# SCH_Hub-USB-Adrian_2025-03-06.net
KiCad netlist of a schematic drawn in EasyEDA
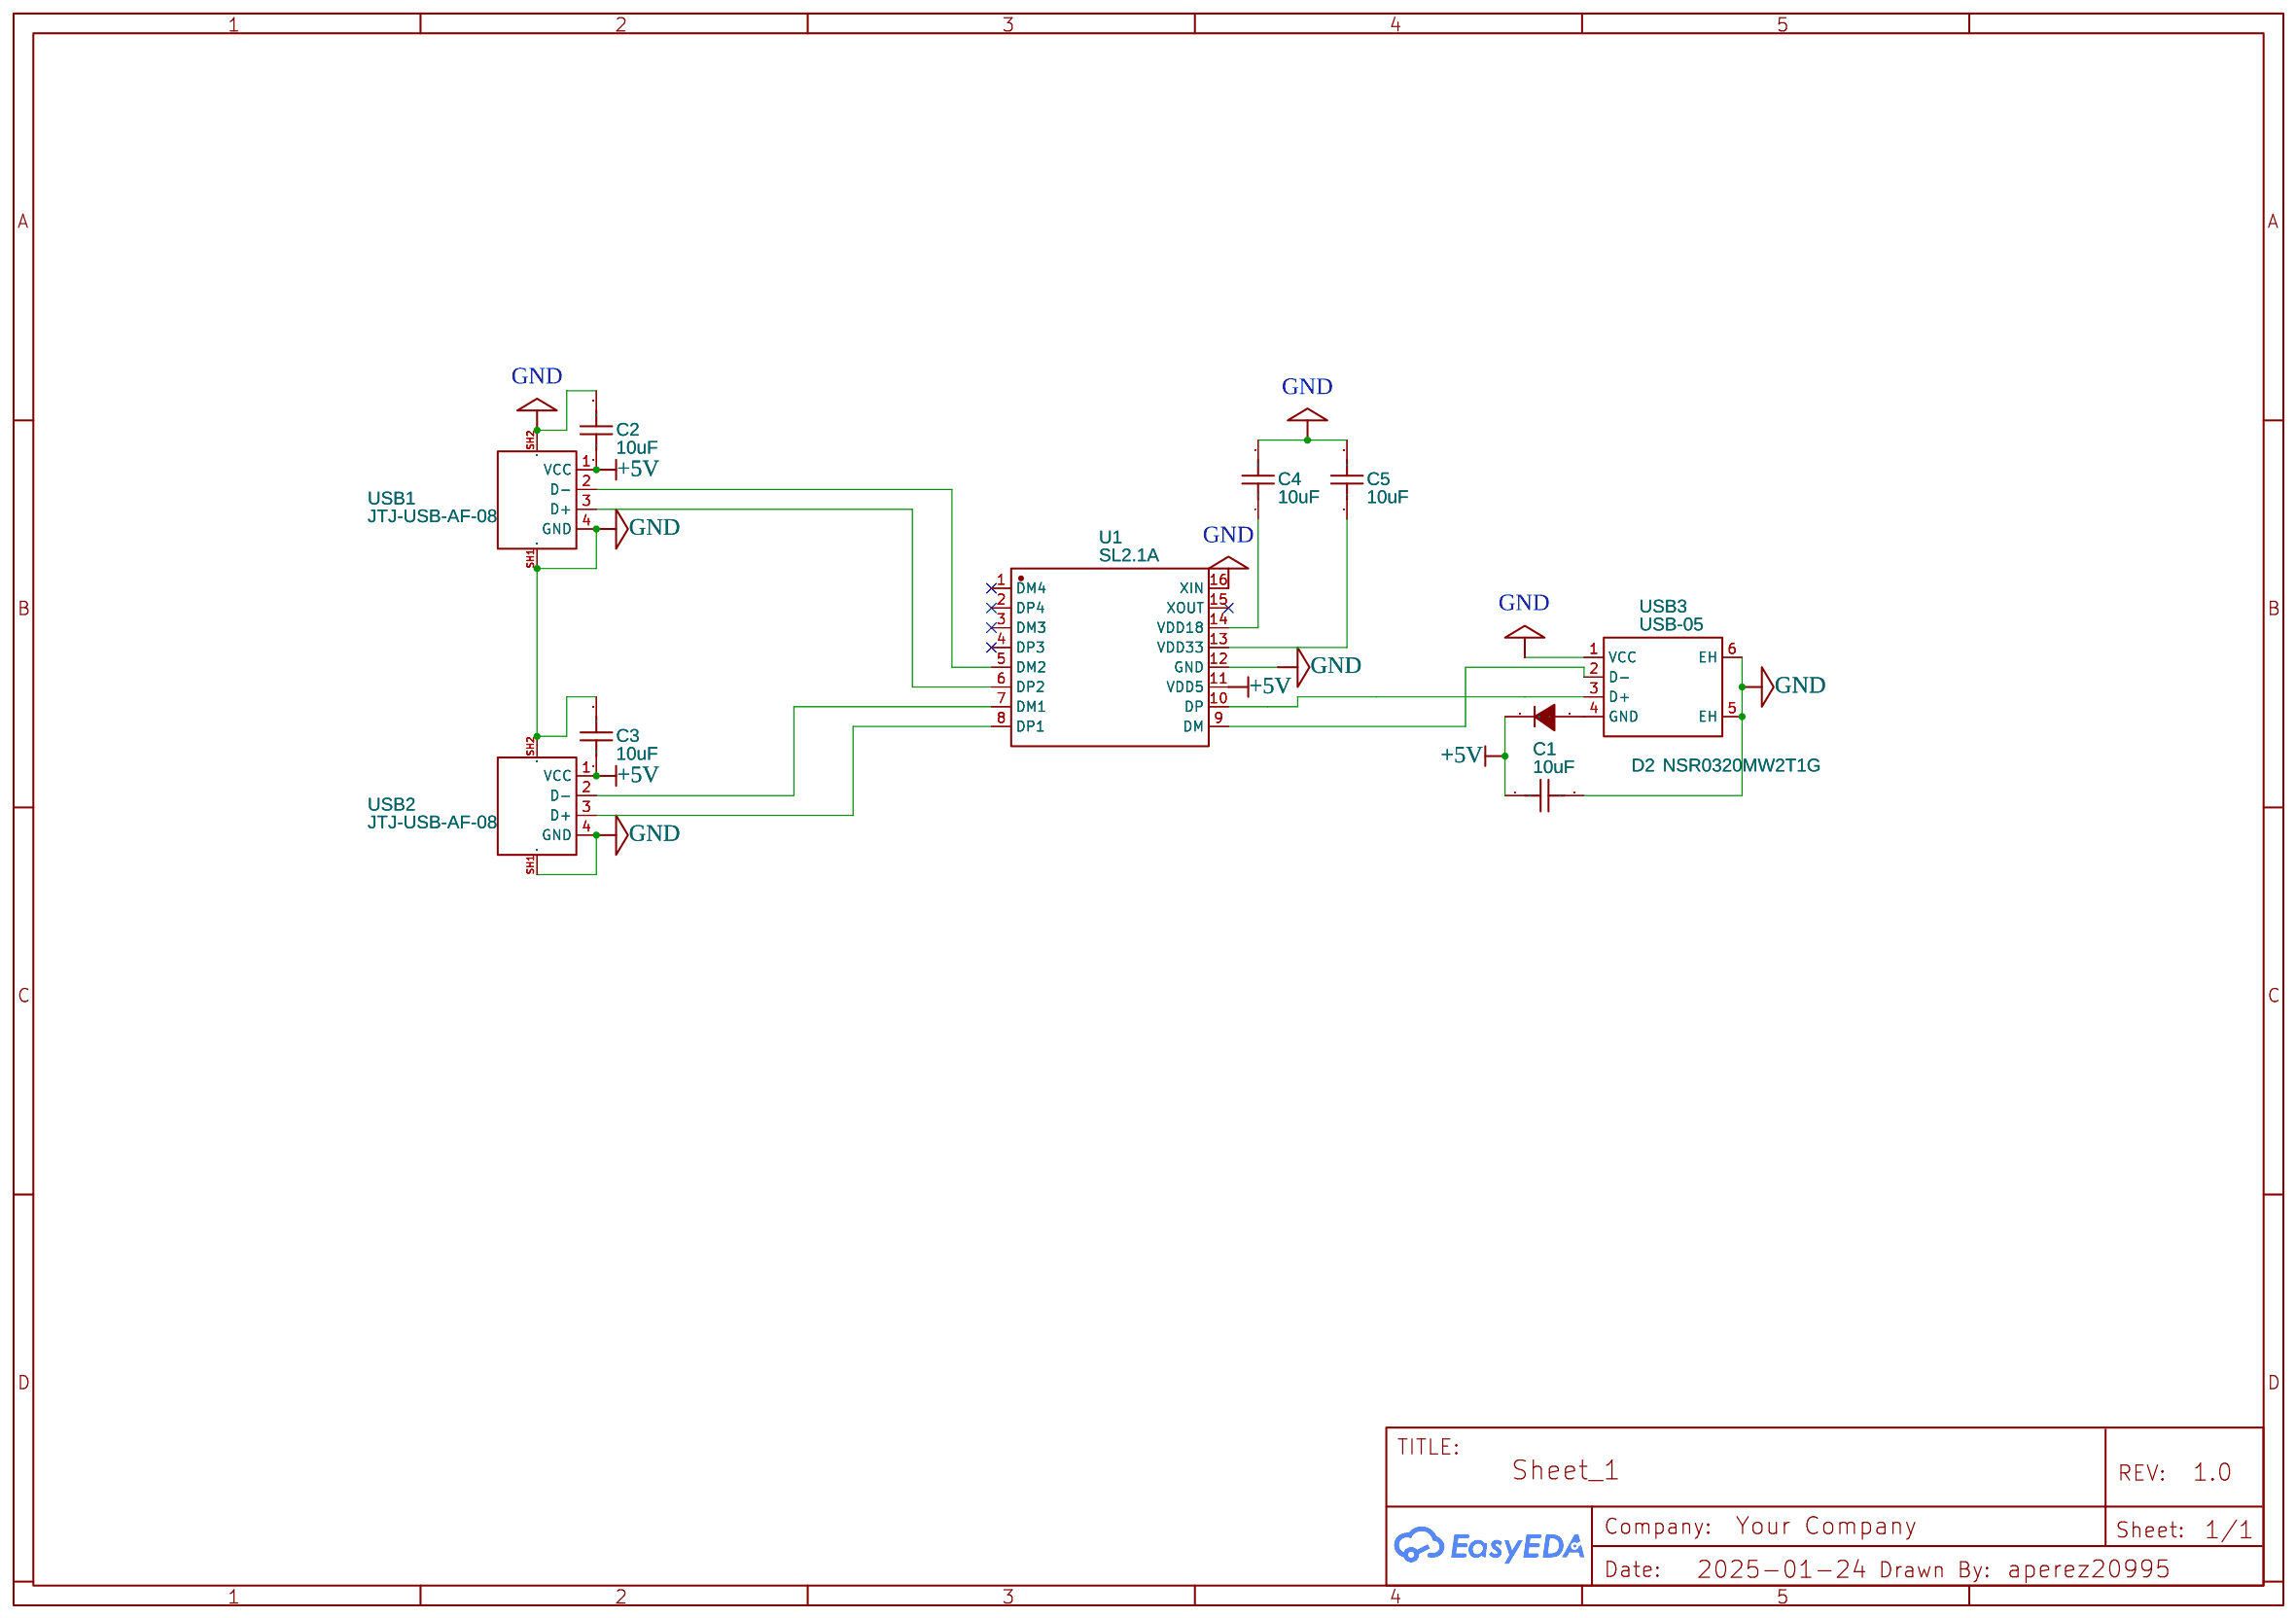
[diagram p0: schematic sheet]

(export (version "E")
  (design (tool "Eeschema 10.0.6"))
  (components
    (comp (ref "C1")
      (value "10uF")
      (fields
        (field (name "Manufacturer Part") "CL10A106KP8NNNC")
        (field (name "Manufacturer") "SAMSUNG(三星)")
      )
      (libsource (lib "") (part "CL10A106KP8NNNC_1"))
    )
    (comp (ref "C2")
      (value "10uF")
      (fields
        (field (name "Manufacturer Part") "CL10A106KP8NNNC")
        (field (name "Manufacturer") "SAMSUNG(三星)")
      )
      (libsource (lib "") (part "CL10A106KP8NNNC"))
    )
    (comp (ref "C3")
      (value "10uF")
      (fields
        (field (name "Manufacturer Part") "CL10A106KP8NNNC")
        (field (name "Manufacturer") "SAMSUNG(三星)")
      )
      (libsource (lib "") (part "CL10A106KP8NNNC"))
    )
    (comp (ref "C4")
      (value "10uF")
      (fields
        (field (name "Manufacturer Part") "CL10A106KP8NNNC")
        (field (name "Manufacturer") "SAMSUNG(三星)")
      )
      (libsource (lib "") (part "CL10A106KP8NNNC"))
    )
    (comp (ref "C5")
      (value "10uF")
      (fields
        (field (name "Manufacturer Part") "CL10A106KP8NNNC")
        (field (name "Manufacturer") "SAMSUNG(三星)")
      )
      (libsource (lib "") (part "CL10A106KP8NNNC"))
    )
    (comp (ref "D2")
      (value "NSR0320MW2T1G")
      (fields (field (name "Manufacturer") "onsemi(安森美)"))
      (libsource (lib "") (part "NSR0320MW2T1G"))
    )
    (comp (ref "U1")
      (value "SL2.1A")
      (fields (field (name "Manufacturer") "CoreChips(和芯润德)"))
      (libsource (lib "") (part "SL2.1A"))
    )
    (comp (ref "USB1")
      (value "JTJ-USB-AF-08")
      (fields (field (name "Manufacturer Part") "902-131A1011D10100") (field (name "Manufacturer") "精拓金"))
      (libsource (lib "") (part "JTJ-USB-AF-08"))
    )
    (comp (ref "USB2")
      (value "JTJ-USB-AF-08")
      (fields (field (name "Manufacturer Part") "902-131A1011D10100") (field (name "Manufacturer") "精拓金"))
      (libsource (lib "") (part "JTJ-USB-AF-08"))
    )
    (comp (ref "USB3")
      (value "USB-05")
      (fields (field (name "Manufacturer") "SOFNG(硕方)"))
      (libsource (lib "") (part "USB-05"))
    )
  )
  (nets
    (net (code "1") (name "+5V") (class "Default")
      (node (ref "C1") (pin "1") (pinfunction "1_1") (pintype "unspecified"))
      (node (ref "C2") (pin "1") (pinfunction "1_1") (pintype "unspecified"))
      (node (ref "C3") (pin "1") (pinfunction "1_1") (pintype "unspecified"))
      (node (ref "D2") (pin "1") (pinfunction "C_1") (pintype "unspecified"))
      (node (ref "U1") (pin "11") (pinfunction "VDD5_11") (pintype "unspecified"))
      (node (ref "USB1") (pin "1") (pinfunction "VCC_1") (pintype "input"))
      (node (ref "USB2") (pin "1") (pinfunction "VCC_1") (pintype "input"))
    )
    (net (code "2") (name "GND") (class "Default")
      (node (ref "C1") (pin "2") (pinfunction "2_2") (pintype "unspecified"))
      (node (ref "C2") (pin "2") (pinfunction "2_2") (pintype "unspecified"))
      (node (ref "C3") (pin "2") (pinfunction "2_2") (pintype "unspecified"))
      (node (ref "C4") (pin "2") (pinfunction "2_2") (pintype "unspecified"))
      (node (ref "C5") (pin "2") (pinfunction "2_2") (pintype "unspecified"))
      (node (ref "U1") (pin "12") (pinfunction "GND_12") (pintype "unspecified"))
      (node (ref "U1") (pin "16") (pinfunction "XIN_16") (pintype "unspecified"))
      (node (ref "USB1") (pin "4") (pinfunction "GND_4") (pintype "input"))
      (node (ref "USB1") (pin "SH1") (pinfunction "SH1_SH1") (pintype "unspecified"))
      (node (ref "USB1") (pin "SH2") (pinfunction "SH2_SH2") (pintype "unspecified"))
      (node (ref "USB2") (pin "4") (pinfunction "GND_4") (pintype "input"))
      (node (ref "USB2") (pin "SH1") (pinfunction "SH1_SH1") (pintype "unspecified"))
      (node (ref "USB2") (pin "SH2") (pinfunction "SH2_SH2") (pintype "unspecified"))
      (node (ref "USB3") (pin "1") (pinfunction "VCC_1") (pintype "input"))
      (node (ref "USB3") (pin "5") (pinfunction "EH_5") (pintype "unspecified"))
      (node (ref "USB3") (pin "6") (pinfunction "EH_6") (pintype "unspecified"))
    )
    (net (code "3") (name "Net-(D2-A)") (class "Default")
      (node (ref "D2") (pin "2") (pinfunction "A_2") (pintype "unspecified"))
      (node (ref "USB3") (pin "4") (pinfunction "GND_4") (pintype "input"))
    )
    (net (code "4") (name "Net-(U1-DM)") (class "Default")
      (node (ref "U1") (pin "9") (pinfunction "DM_9") (pintype "unspecified"))
      (node (ref "USB3") (pin "2") (pinfunction "D-_2") (pintype "input"))
    )
    (net (code "5") (name "Net-(U1-DM1)") (class "Default")
      (node (ref "U1") (pin "7") (pinfunction "DM1_7") (pintype "unspecified"))
      (node (ref "USB2") (pin "2") (pinfunction "D-_2") (pintype "input"))
    )
    (net (code "6") (name "Net-(U1-DM2)") (class "Default")
      (node (ref "U1") (pin "5") (pinfunction "DM2_5") (pintype "unspecified"))
      (node (ref "USB1") (pin "2") (pinfunction "D-_2") (pintype "input"))
    )
    (net (code "7") (name "Net-(U1-DP)") (class "Default")
      (node (ref "U1") (pin "10") (pinfunction "DP_10") (pintype "unspecified"))
      (node (ref "USB3") (pin "3") (pinfunction "D+_3") (pintype "input"))
    )
    (net (code "8") (name "Net-(U1-DP1)") (class "Default")
      (node (ref "U1") (pin "8") (pinfunction "DP1_8") (pintype "unspecified"))
      (node (ref "USB2") (pin "3") (pinfunction "D+_3") (pintype "input"))
    )
    (net (code "9") (name "Net-(U1-DP2)") (class "Default")
      (node (ref "U1") (pin "6") (pinfunction "DP2_6") (pintype "unspecified"))
      (node (ref "USB1") (pin "3") (pinfunction "D+_3") (pintype "input"))
    )
    (net (code "10") (name "Net-(U1-VDD18)") (class "Default")
      (node (ref "C4") (pin "1") (pinfunction "1_1") (pintype "unspecified"))
      (node (ref "U1") (pin "14") (pinfunction "VDD18_14") (pintype "unspecified"))
    )
    (net (code "11") (name "Net-(U1-VDD33)") (class "Default")
      (node (ref "C5") (pin "1") (pinfunction "1_1") (pintype "unspecified"))
      (node (ref "U1") (pin "13") (pinfunction "VDD33_13") (pintype "unspecified"))
    )
    (net (code "12") (name "unconnected-(U1-DM3-Pad3)") (class "Default")
      (node (ref "U1") (pin "3") (pinfunction "DM3_3") (pintype "unspecified+no_connect"))
    )
    (net (code "13") (name "unconnected-(U1-DM4-Pad1)") (class "Default")
      (node (ref "U1") (pin "1") (pinfunction "DM4_1") (pintype "unspecified+no_connect"))
    )
    (net (code "14") (name "unconnected-(U1-DP3-Pad4)") (class "Default")
      (node (ref "U1") (pin "4") (pinfunction "DP3_4") (pintype "unspecified+no_connect"))
    )
    (net (code "15") (name "unconnected-(U1-DP4-Pad2)") (class "Default")
      (node (ref "U1") (pin "2") (pinfunction "DP4_2") (pintype "unspecified+no_connect"))
    )
    (net (code "16") (name "unconnected-(U1-XOUT-Pad15)") (class "Default")
      (node (ref "U1") (pin "15") (pinfunction "XOUT_15") (pintype "unspecified+no_connect"))
    )
  )
)
